# OpenPLCv0_2_0_AnalogueOutput.net
KiCad netlist of a schematic drawn in Altium Designer
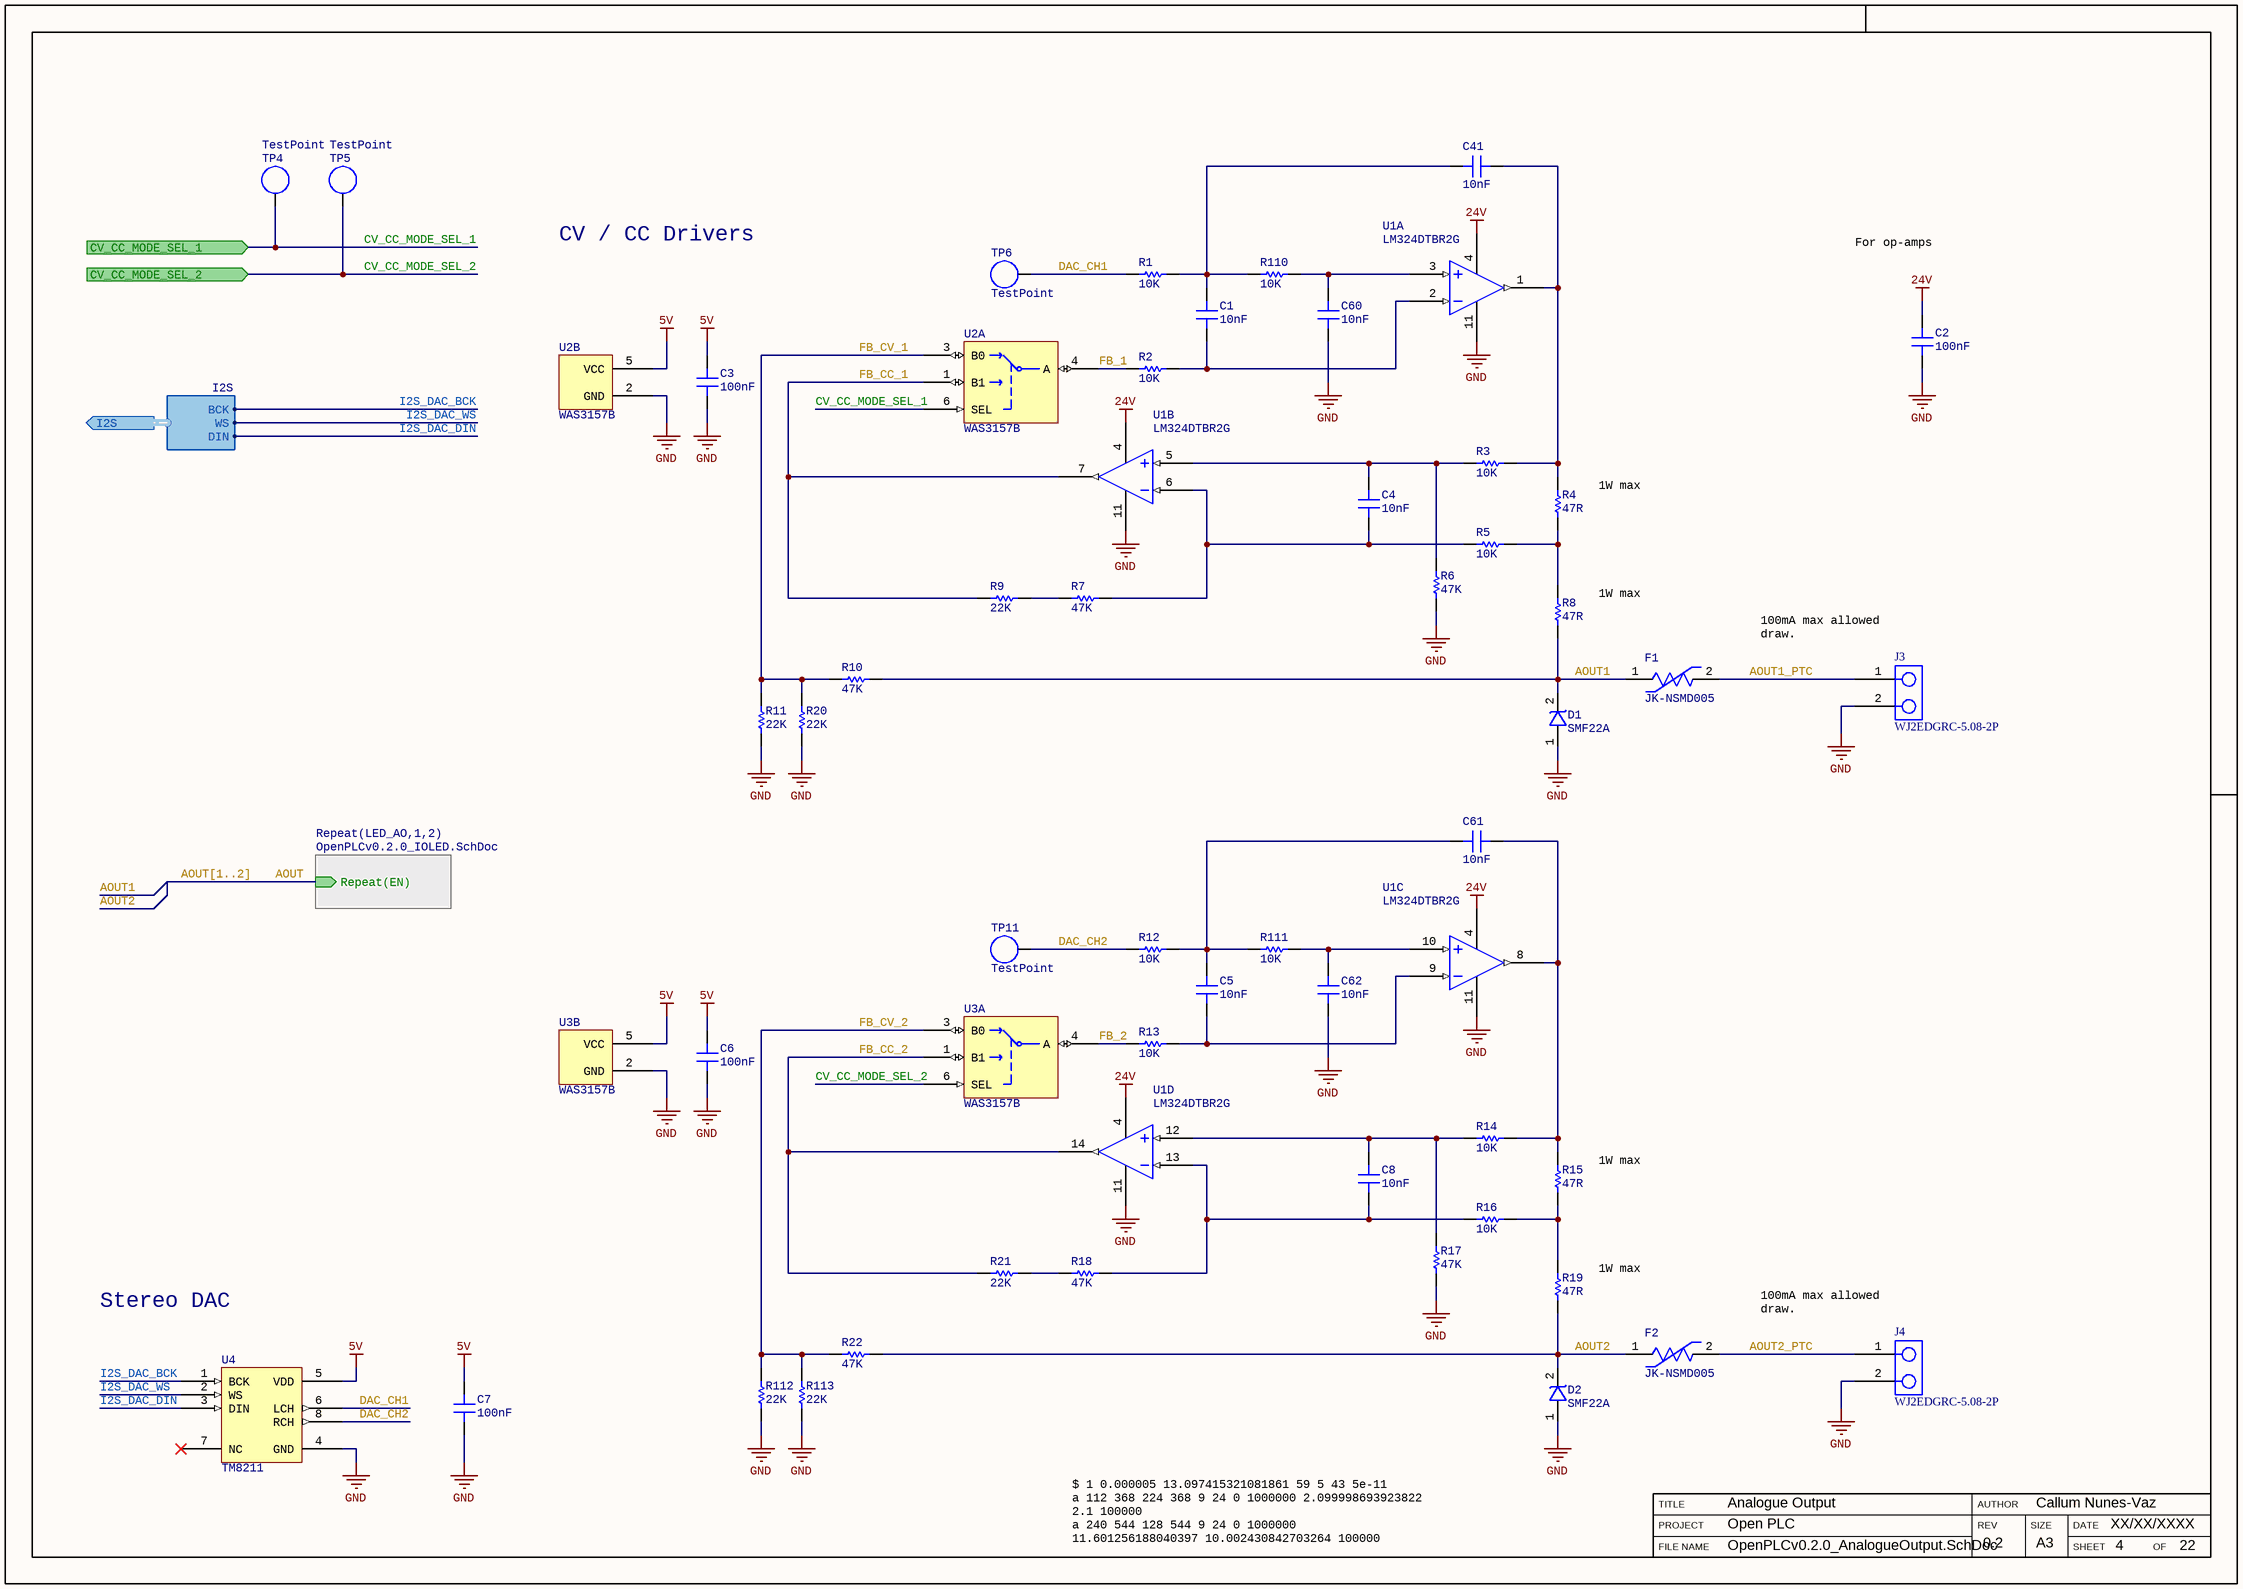
[diagram p0: OpenPLCv0.2.0_AnalogueOutput.SchDoc]

(export (version "E")
  (design (tool "Eeschema 10.0.6"))
  (components
    (comp (ref "C1")
      (value "CC0402KRX7R9BB103")
      (footprint "SMD_CAP_0402(1005)_N")
      (description "10nF ±10% 50V X7R 0402 Multilayer Ceramic Capacitors MLCC - SMD/SMT RoHS")
      (fields (field (name "TOLERANCE") "10%") (field (name "CAPACITANCE") "10nF"))
      (libsource (lib "BrauV2_Capacitor") (part "10nF 0402 50V 10%"))
    )
    (comp (ref "C2")
      (value "CC0402KRX5R9BB104")
      (footprint "SMD_CAP_0402(1005)_N")
      (description "100nF ±10% 50V X5R 0402 Multilayer Ceramic Capacitors MLCC - SMD/SMT RoHS")
      (fields (field (name "TOLERANCE") "10%") (field (name "CAPACITANCE") "100nF"))
      (libsource (lib "BrauV2_Capacitor") (part "100nF 0402 50V 10%"))
    )
    (comp (ref "C3")
      (value "CC0402KRX5R6BB104")
      (footprint "SMD_CAP_0402(1005)_N")
      (description "100nF ±10% 10V X5R 0402 Multilayer Ceramic Capacitors MLCC - SMD/SMT RoHS")
      (fields (field (name "TOLERANCE") "10%") (field (name "CAPACITANCE") "100nF"))
      (libsource (lib "BrauV2_Capacitor") (part "100nF 0402 10V 10%"))
    )
    (comp (ref "C4")
      (value "CC0402KRX7R9BB103")
      (footprint "SMD_CAP_0402(1005)_N")
      (description "10nF ±10% 50V X7R 0402 Multilayer Ceramic Capacitors MLCC - SMD/SMT RoHS")
      (fields (field (name "TOLERANCE") "10%") (field (name "CAPACITANCE") "10nF"))
      (libsource (lib "BrauV2_Capacitor") (part "10nF 0402 50V 10%"))
    )
    (comp (ref "C5")
      (value "CC0402KRX7R9BB103")
      (footprint "SMD_CAP_0402(1005)_N")
      (description "10nF ±10% 50V X7R 0402 Multilayer Ceramic Capacitors MLCC - SMD/SMT RoHS")
      (fields (field (name "TOLERANCE") "10%") (field (name "CAPACITANCE") "10nF"))
      (libsource (lib "BrauV2_Capacitor") (part "10nF 0402 50V 10%"))
    )
    (comp (ref "C6")
      (value "CC0402KRX5R6BB104")
      (footprint "SMD_CAP_0402(1005)_N")
      (description "100nF ±10% 10V X5R 0402 Multilayer Ceramic Capacitors MLCC - SMD/SMT RoHS")
      (fields (field (name "TOLERANCE") "10%") (field (name "CAPACITANCE") "100nF"))
      (libsource (lib "BrauV2_Capacitor") (part "100nF 0402 10V 10%"))
    )
    (comp (ref "C7")
      (value "CC0402KRX5R6BB104")
      (footprint "SMD_CAP_0402(1005)_N")
      (description "100nF ±10% 10V X5R 0402 Multilayer Ceramic Capacitors MLCC - SMD/SMT RoHS")
      (fields (field (name "TOLERANCE") "10%") (field (name "CAPACITANCE") "100nF"))
      (libsource (lib "BrauV2_Capacitor") (part "100nF 0402 10V 10%"))
    )
    (comp (ref "C8")
      (value "CC0402KRX7R9BB103")
      (footprint "SMD_CAP_0402(1005)_N")
      (description "10nF ±10% 50V X7R 0402 Multilayer Ceramic Capacitors MLCC - SMD/SMT RoHS")
      (fields (field (name "TOLERANCE") "10%") (field (name "CAPACITANCE") "10nF"))
      (libsource (lib "BrauV2_Capacitor") (part "10nF 0402 50V 10%"))
    )
    (comp (ref "C41")
      (value "CC0402KRX7R9BB103")
      (footprint "SMD_CAP_0402(1005)_N")
      (description "10nF ±10% 50V X7R 0402 Multilayer Ceramic Capacitors MLCC - SMD/SMT RoHS")
      (fields (field (name "TOLERANCE") "10%") (field (name "CAPACITANCE") "10nF"))
      (libsource (lib "BrauV2_Capacitor") (part "10nF 0402 50V 10%"))
    )
    (comp (ref "C60")
      (value "CC0402KRX7R9BB103")
      (footprint "SMD_CAP_0402(1005)_N")
      (description "10nF ±10% 50V X7R 0402 Multilayer Ceramic Capacitors MLCC - SMD/SMT RoHS")
      (fields (field (name "TOLERANCE") "10%") (field (name "CAPACITANCE") "10nF"))
      (libsource (lib "BrauV2_Capacitor") (part "10nF 0402 50V 10%"))
    )
    (comp (ref "C61")
      (value "CC0402KRX7R9BB103")
      (footprint "SMD_CAP_0402(1005)_N")
      (description "10nF ±10% 50V X7R 0402 Multilayer Ceramic Capacitors MLCC - SMD/SMT RoHS")
      (fields (field (name "TOLERANCE") "10%") (field (name "CAPACITANCE") "10nF"))
      (libsource (lib "BrauV2_Capacitor") (part "10nF 0402 50V 10%"))
    )
    (comp (ref "C62")
      (value "CC0402KRX7R9BB103")
      (footprint "SMD_CAP_0402(1005)_N")
      (description "10nF ±10% 50V X7R 0402 Multilayer Ceramic Capacitors MLCC - SMD/SMT RoHS")
      (fields (field (name "TOLERANCE") "10%") (field (name "CAPACITANCE") "10nF"))
      (libsource (lib "BrauV2_Capacitor") (part "10nF 0402 50V 10%"))
    )
    (comp (ref "D1")
      (value "SMF22A")
      (footprint "SOD-123FL")
      (description "Unidirectional 22V 24.4V 35.5V 5.6A SOD-123F TVS RoHS")
      (libsource (lib "BrauV2") (part "SMF22A"))
    )
    (comp (ref "D2")
      (value "SMF22A")
      (footprint "SOD-123FL")
      (description "Unidirectional 22V 24.4V 35.5V 5.6A SOD-123F TVS RoHS")
      (libsource (lib "BrauV2") (part "SMF22A"))
    )
    (comp (ref "F1")
      (value "JK-NSMD005")
      (footprint "SMD_RES_1206(3216)_N")
      (description "60V 150mA 1.5s 1206 PTC Resettable Fuses RoHS")
      (libsource (lib "BrauV2_Resistor") (part "JK-NSMD005"))
    )
    (comp (ref "F2")
      (value "JK-NSMD005")
      (footprint "SMD_RES_1206(3216)_N")
      (description "60V 150mA 1.5s 1206 PTC Resettable Fuses RoHS")
      (libsource (lib "BrauV2_Resistor") (part "JK-NSMD005"))
    )
    (comp (ref "J3")
      (value "WJ2EDGRC-5.08-2P")
      (footprint "796638-2_BoardEdgeAlt")
      (description "Covered（4Sided） 2 1 0.200\"（5.08mm） 2 P=5.08mm Pluggable System Terminal Block RoHS")
      (libsource (lib "OpenPLCv0.2.0_Connector") (part "WJ2EDGRC-5.08-2P"))
    )
    (comp (ref "J4")
      (value "WJ2EDGRC-5.08-2P")
      (footprint "796638-2_BoardEdgeAlt")
      (description "Covered（4Sided） 2 1 0.200\"（5.08mm） 2 P=5.08mm Pluggable System Terminal Block RoHS")
      (libsource (lib "OpenPLCv0.2.0_Connector") (part "WJ2EDGRC-5.08-2P"))
    )
    (comp (ref "R1")
      (value "RC0402FR-0710KL")
      (footprint "SMD_RES_0402(1005)_N")
      (description "10kΩ ±1% 1/16W ±100ppm/℃ 0402 Chip Resistor - Surface Mount RoHS")
      (fields (field (name "TOLERANCE") "1%") (field (name "RESISTANCE") "10K"))
      (libsource (lib "BrauV2_Resistor") (part "10K 0402 1% 1/16W"))
    )
    (comp (ref "R2")
      (value "RC0402FR-0710KL")
      (footprint "SMD_RES_0402(1005)_N")
      (description "10kΩ ±1% 1/16W ±100ppm/℃ 0402 Chip Resistor - Surface Mount RoHS")
      (fields (field (name "TOLERANCE") "1%") (field (name "RESISTANCE") "10K"))
      (libsource (lib "BrauV2_Resistor") (part "10K 0402 1% 1/16W"))
    )
    (comp (ref "R3")
      (value "RC0402FR-0710KL")
      (footprint "SMD_RES_0402(1005)_N")
      (description "10kΩ ±1% 1/16W ±100ppm/℃ 0402 Chip Resistor - Surface Mount RoHS")
      (fields (field (name "TOLERANCE") "1%") (field (name "RESISTANCE") "10K"))
      (libsource (lib "BrauV2_Resistor") (part "10K 0402 1% 1/16W"))
    )
    (comp (ref "R4")
      (value "AC2512FK-0747RL")
      (footprint "SMD_RES_2512(6432)_N")
      (description "47Ω ±1% 1W ±100ppm/℃ 2512 Chip Resistor - Surface Mount RoHS")
      (fields (field (name "TOLERANCE") "1%") (field (name "RESISTANCE") "47R"))
      (libsource (lib "BrauV2_Resistor") (part "47R 2512 1% 1W"))
    )
    (comp (ref "R5")
      (value "RC0402FR-0710KL")
      (footprint "SMD_RES_0402(1005)_N")
      (description "10kΩ ±1% 1/16W ±100ppm/℃ 0402 Chip Resistor - Surface Mount RoHS")
      (fields (field (name "TOLERANCE") "1%") (field (name "RESISTANCE") "10K"))
      (libsource (lib "BrauV2_Resistor") (part "10K 0402 1% 1/16W"))
    )
    (comp (ref "R6")
      (value "RC0402FR-0747KL")
      (footprint "SMD_RES_0402(1005)_N")
      (description "47kΩ ±1% 1/16W ±100ppm/℃ 0402 Chip Resistor - Surface Mount RoHS")
      (fields (field (name "TOLERANCE") "1%") (field (name "RESISTANCE") "47K"))
      (libsource (lib "BrauV2_Resistor") (part "47K 0402 1% 1/16W"))
    )
    (comp (ref "R7")
      (value "RC0402FR-0747KL")
      (footprint "SMD_RES_0402(1005)_N")
      (description "47kΩ ±1% 1/16W ±100ppm/℃ 0402 Chip Resistor - Surface Mount RoHS")
      (fields (field (name "TOLERANCE") "1%") (field (name "RESISTANCE") "47K"))
      (libsource (lib "BrauV2_Resistor") (part "47K 0402 1% 1/16W"))
    )
    (comp (ref "R8")
      (value "AC2512FK-0747RL")
      (footprint "SMD_RES_2512(6432)_N")
      (description "47Ω ±1% 1W ±100ppm/℃ 2512 Chip Resistor - Surface Mount RoHS")
      (fields (field (name "TOLERANCE") "1%") (field (name "RESISTANCE") "47R"))
      (libsource (lib "BrauV2_Resistor") (part "47R 2512 1% 1W"))
    )
    (comp (ref "R9")
      (value "RC0402FR-0722KL")
      (footprint "SMD_RES_0402(1005)_N")
      (description "22kΩ ±1% 1/16W ±100ppm/℃ 0402 Chip Resistor - Surface Mount RoHS")
      (fields (field (name "TOLERANCE") "1%") (field (name "RESISTANCE") "22K"))
      (libsource (lib "BrauV2_Resistor") (part "22K 0402 1% 1/16W"))
    )
    (comp (ref "R10")
      (value "RC0402FR-0747KL")
      (footprint "SMD_RES_0402(1005)_N")
      (description "47kΩ ±1% 1/16W ±100ppm/℃ 0402 Chip Resistor - Surface Mount RoHS")
      (fields (field (name "TOLERANCE") "1%") (field (name "RESISTANCE") "47K"))
      (libsource (lib "BrauV2_Resistor") (part "47K 0402 1% 1/16W"))
    )
    (comp (ref "R11")
      (value "RC0402FR-0722KL")
      (footprint "SMD_RES_0402(1005)_N")
      (description "22kΩ ±1% 1/16W ±100ppm/℃ 0402 Chip Resistor - Surface Mount RoHS")
      (fields (field (name "TOLERANCE") "1%") (field (name "RESISTANCE") "22K"))
      (libsource (lib "BrauV2_Resistor") (part "22K 0402 1% 1/16W"))
    )
    (comp (ref "R12")
      (value "RC0402FR-0710KL")
      (footprint "SMD_RES_0402(1005)_N")
      (description "10kΩ ±1% 1/16W ±100ppm/℃ 0402 Chip Resistor - Surface Mount RoHS")
      (fields (field (name "TOLERANCE") "1%") (field (name "RESISTANCE") "10K"))
      (libsource (lib "BrauV2_Resistor") (part "10K 0402 1% 1/16W"))
    )
    (comp (ref "R13")
      (value "RC0402FR-0710KL")
      (footprint "SMD_RES_0402(1005)_N")
      (description "10kΩ ±1% 1/16W ±100ppm/℃ 0402 Chip Resistor - Surface Mount RoHS")
      (fields (field (name "TOLERANCE") "1%") (field (name "RESISTANCE") "10K"))
      (libsource (lib "BrauV2_Resistor") (part "10K 0402 1% 1/16W"))
    )
    (comp (ref "R14")
      (value "RC0402FR-0710KL")
      (footprint "SMD_RES_0402(1005)_N")
      (description "10kΩ ±1% 1/16W ±100ppm/℃ 0402 Chip Resistor - Surface Mount RoHS")
      (fields (field (name "TOLERANCE") "1%") (field (name "RESISTANCE") "10K"))
      (libsource (lib "BrauV2_Resistor") (part "10K 0402 1% 1/16W"))
    )
    (comp (ref "R15")
      (value "AC2512FK-0747RL")
      (footprint "SMD_RES_2512(6432)_N")
      (description "47Ω ±1% 1W ±100ppm/℃ 2512 Chip Resistor - Surface Mount RoHS")
      (fields (field (name "TOLERANCE") "1%") (field (name "RESISTANCE") "47R"))
      (libsource (lib "BrauV2_Resistor") (part "47R 2512 1% 1W"))
    )
    (comp (ref "R16")
      (value "RC0402FR-0710KL")
      (footprint "SMD_RES_0402(1005)_N")
      (description "10kΩ ±1% 1/16W ±100ppm/℃ 0402 Chip Resistor - Surface Mount RoHS")
      (fields (field (name "TOLERANCE") "1%") (field (name "RESISTANCE") "10K"))
      (libsource (lib "BrauV2_Resistor") (part "10K 0402 1% 1/16W"))
    )
    (comp (ref "R17")
      (value "RC0402FR-0747KL")
      (footprint "SMD_RES_0402(1005)_N")
      (description "47kΩ ±1% 1/16W ±100ppm/℃ 0402 Chip Resistor - Surface Mount RoHS")
      (fields (field (name "TOLERANCE") "1%") (field (name "RESISTANCE") "47K"))
      (libsource (lib "BrauV2_Resistor") (part "47K 0402 1% 1/16W"))
    )
    (comp (ref "R18")
      (value "RC0402FR-0747KL")
      (footprint "SMD_RES_0402(1005)_N")
      (description "47kΩ ±1% 1/16W ±100ppm/℃ 0402 Chip Resistor - Surface Mount RoHS")
      (fields (field (name "TOLERANCE") "1%") (field (name "RESISTANCE") "47K"))
      (libsource (lib "BrauV2_Resistor") (part "47K 0402 1% 1/16W"))
    )
    (comp (ref "R19")
      (value "AC2512FK-0747RL")
      (footprint "SMD_RES_2512(6432)_N")
      (description "47Ω ±1% 1W ±100ppm/℃ 2512 Chip Resistor - Surface Mount RoHS")
      (fields (field (name "TOLERANCE") "1%") (field (name "RESISTANCE") "47R"))
      (libsource (lib "BrauV2_Resistor") (part "47R 2512 1% 1W"))
    )
    (comp (ref "R20")
      (value "RC0402FR-0722KL")
      (footprint "SMD_RES_0402(1005)_N")
      (description "22kΩ ±1% 1/16W ±100ppm/℃ 0402 Chip Resistor - Surface Mount RoHS")
      (fields (field (name "TOLERANCE") "1%") (field (name "RESISTANCE") "22K"))
      (libsource (lib "BrauV2_Resistor") (part "22K 0402 1% 1/16W"))
    )
    (comp (ref "R21")
      (value "RC0402FR-0722KL")
      (footprint "SMD_RES_0402(1005)_N")
      (description "22kΩ ±1% 1/16W ±100ppm/℃ 0402 Chip Resistor - Surface Mount RoHS")
      (fields (field (name "TOLERANCE") "1%") (field (name "RESISTANCE") "22K"))
      (libsource (lib "BrauV2_Resistor") (part "22K 0402 1% 1/16W"))
    )
    (comp (ref "R22")
      (value "RC0402FR-0747KL")
      (footprint "SMD_RES_0402(1005)_N")
      (description "47kΩ ±1% 1/16W ±100ppm/℃ 0402 Chip Resistor - Surface Mount RoHS")
      (fields (field (name "TOLERANCE") "1%") (field (name "RESISTANCE") "47K"))
      (libsource (lib "BrauV2_Resistor") (part "47K 0402 1% 1/16W"))
    )
    (comp (ref "R110")
      (value "RC0402FR-0710KL")
      (footprint "SMD_RES_0402(1005)_N")
      (description "10kΩ ±1% 1/16W ±100ppm/℃ 0402 Chip Resistor - Surface Mount RoHS")
      (fields (field (name "TOLERANCE") "1%") (field (name "RESISTANCE") "10K"))
      (libsource (lib "BrauV2_Resistor") (part "10K 0402 1% 1/16W"))
    )
    (comp (ref "R111")
      (value "RC0402FR-0710KL")
      (footprint "SMD_RES_0402(1005)_N")
      (description "10kΩ ±1% 1/16W ±100ppm/℃ 0402 Chip Resistor - Surface Mount RoHS")
      (fields (field (name "TOLERANCE") "1%") (field (name "RESISTANCE") "10K"))
      (libsource (lib "BrauV2_Resistor") (part "10K 0402 1% 1/16W"))
    )
    (comp (ref "R112")
      (value "RC0402FR-0722KL")
      (footprint "SMD_RES_0402(1005)_N")
      (description "22kΩ ±1% 1/16W ±100ppm/℃ 0402 Chip Resistor - Surface Mount RoHS")
      (fields (field (name "TOLERANCE") "1%") (field (name "RESISTANCE") "22K"))
      (libsource (lib "BrauV2_Resistor") (part "22K 0402 1% 1/16W"))
    )
    (comp (ref "R113")
      (value "RC0402FR-0722KL")
      (footprint "SMD_RES_0402(1005)_N")
      (description "22kΩ ±1% 1/16W ±100ppm/℃ 0402 Chip Resistor - Surface Mount RoHS")
      (fields (field (name "TOLERANCE") "1%") (field (name "RESISTANCE") "22K"))
      (libsource (lib "BrauV2_Resistor") (part "22K 0402 1% 1/16W"))
    )
    (comp (ref "TP4")
      (value "TestPoint")
      (footprint "Pad")
      (libsource (lib "OpenPLCv0.2.0_Misc") (part "Test point"))
    )
    (comp (ref "TP5")
      (value "TestPoint")
      (footprint "Pad")
      (libsource (lib "OpenPLCv0.2.0_Misc") (part "Test point"))
    )
    (comp (ref "TP6")
      (value "TestPoint")
      (footprint "Pad")
      (libsource (lib "OpenPLCv0.2.0_Misc") (part "Test point"))
    )
    (comp (ref "TP11")
      (value "TestPoint")
      (footprint "Pad")
      (libsource (lib "OpenPLCv0.2.0_Misc") (part "Test point"))
    )
    (comp (ref "U1")
      (value "LM324DTBR2G")
      (footprint "TSSOP-14")
      (description "General Purpose 4 3V ~ 32V, ±1.5V ~ 16V 1MHz 0.6 V/us TSSOP-14 Operational Amplifiers RoHS")
      (libsource (lib "BrauV2_IC") (part "LM324DTBR2G"))
    )
    (comp (ref "U2")
      (value "WAS3157B")
      (footprint "SOT23-6")
      (description "5.5Ω, 400MHz Bandwidth, SPDT Analog Switch SOT23-6")
      (libsource (lib "BrauV2_IC") (part "WAS3157B"))
    )
    (comp (ref "U3")
      (value "WAS3157B")
      (footprint "SOT23-6")
      (description "5.5Ω, 400MHz Bandwidth, SPDT Analog Switch SOT23-6")
      (libsource (lib "BrauV2_IC") (part "WAS3157B"))
    )
    (comp (ref "U4")
      (value "TM8211")
      (footprint "SOIC-8-3.9mm")
      (description "Digital To Analog Converters (DACs) 16bit I2S")
      (libsource (lib "BrauV2_IC") (part "TM8211"))
    )
  )
  (nets
    (net (code "3") (name "/AOUT1") (class "Default")
      (node (ref "D1") (pin "2") (pinfunction "CATHODE_2") (pintype "passive"))
      (node (ref "F1") (pin "1") (pinfunction "1_1") (pintype "passive"))
      (node (ref "R10") (pin "2") (pinfunction "2_2") (pintype "passive"))
      (node (ref "R8") (pin "1") (pinfunction "1_1") (pintype "passive"))
    )
    (net (code "4") (name "/AOUT1_PTC") (class "Default")
      (node (ref "F1") (pin "2") (pinfunction "2_2") (pintype "passive"))
      (node (ref "J3") (pin "1") (pinfunction "1_1") (pintype "passive"))
    )
    (net (code "5") (name "/AOUT2") (class "Default")
      (node (ref "D2") (pin "2") (pinfunction "CATHODE_2") (pintype "passive"))
      (node (ref "F2") (pin "1") (pinfunction "1_1") (pintype "passive"))
      (node (ref "R19") (pin "1") (pinfunction "1_1") (pintype "passive"))
      (node (ref "R22") (pin "2") (pinfunction "2_2") (pintype "passive"))
    )
    (net (code "6") (name "/AOUT2_PTC") (class "Default")
      (node (ref "F2") (pin "2") (pinfunction "2_2") (pintype "passive"))
      (node (ref "J4") (pin "1") (pinfunction "1_1") (pintype "passive"))
    )
    (net (code "8") (name "/CV_CC_MODE_SEL_1") (class "Default")
      (node (ref "TP4") (pin "1") (pinfunction "1_1") (pintype "passive"))
      (node (ref "U2") (pin "6") (pinfunction "SEL_6") (pintype "input"))
    )
    (net (code "9") (name "/CV_CC_MODE_SEL_2") (class "Default")
      (node (ref "TP5") (pin "1") (pinfunction "1_1") (pintype "passive"))
      (node (ref "U3") (pin "6") (pinfunction "SEL_6") (pintype "input"))
    )
    (net (code "10") (name "/DAC_CH1") (class "Default")
      (node (ref "R1") (pin "1") (pinfunction "1_1") (pintype "passive"))
      (node (ref "TP6") (pin "1") (pinfunction "1_1") (pintype "passive"))
      (node (ref "U4") (pin "6") (pinfunction "LCH_6") (pintype "output"))
    )
    (net (code "11") (name "/DAC_CH2") (class "Default")
      (node (ref "R12") (pin "1") (pinfunction "1_1") (pintype "passive"))
      (node (ref "TP11") (pin "1") (pinfunction "1_1") (pintype "passive"))
      (node (ref "U4") (pin "8") (pinfunction "RCH_8") (pintype "output"))
    )
    (net (code "12") (name "/FB_1") (class "Default")
      (node (ref "R2") (pin "1") (pinfunction "1_1") (pintype "passive"))
      (node (ref "U2") (pin "4") (pinfunction "A_4") (pintype "bidirectional"))
    )
    (net (code "13") (name "/FB_2") (class "Default")
      (node (ref "R13") (pin "1") (pinfunction "1_1") (pintype "passive"))
      (node (ref "U3") (pin "4") (pinfunction "A_4") (pintype "bidirectional"))
    )
    (net (code "14") (name "/FB_CC_1") (class "Default")
      (node (ref "R9") (pin "2") (pinfunction "2_2") (pintype "passive"))
      (node (ref "U1") (pin "7") (pinfunction "VOUT_7") (pintype "output"))
      (node (ref "U2") (pin "1") (pinfunction "B1_1") (pintype "bidirectional"))
    )
    (net (code "15") (name "/FB_CC_2") (class "Default")
      (node (ref "R21") (pin "2") (pinfunction "2_2") (pintype "passive"))
      (node (ref "U1") (pin "14") (pinfunction "VOUT_14") (pintype "output"))
      (node (ref "U3") (pin "1") (pinfunction "B1_1") (pintype "bidirectional"))
    )
    (net (code "16") (name "/FB_CV_1") (class "Default")
      (node (ref "R10") (pin "1") (pinfunction "1_1") (pintype "passive"))
      (node (ref "R11") (pin "2") (pinfunction "2_2") (pintype "passive"))
      (node (ref "R20") (pin "2") (pinfunction "2_2") (pintype "passive"))
      (node (ref "U2") (pin "3") (pinfunction "B0_3") (pintype "bidirectional"))
    )
    (net (code "17") (name "/FB_CV_2") (class "Default")
      (node (ref "R112") (pin "2") (pinfunction "2_2") (pintype "passive"))
      (node (ref "R113") (pin "2") (pinfunction "2_2") (pintype "passive"))
      (node (ref "R22") (pin "1") (pinfunction "1_1") (pintype "passive"))
      (node (ref "U3") (pin "3") (pinfunction "B0_3") (pintype "bidirectional"))
    )
    (net (code "18") (name "/I2S_DAC_BCK") (class "Default")
      (node (ref "U4") (pin "1") (pinfunction "BCK_1") (pintype "input"))
    )
    (net (code "19") (name "/I2S_DAC_DIN") (class "Default")
      (node (ref "U4") (pin "3") (pinfunction "DIN_3") (pintype "input"))
    )
    (net (code "20") (name "/I2S_DAC_WS") (class "Default")
      (node (ref "U4") (pin "2") (pinfunction "WS_2") (pintype "input"))
    )
    (net (code "22") (name "5V") (class "Default")
      (node (ref "C3") (pin "2") (pinfunction "2_2") (pintype "passive"))
      (node (ref "C6") (pin "2") (pinfunction "2_2") (pintype "passive"))
      (node (ref "C7") (pin "2") (pinfunction "2_2") (pintype "passive"))
      (node (ref "U2") (pin "5") (pinfunction "VCC_5") (pintype "power_in"))
      (node (ref "U3") (pin "5") (pinfunction "VCC_5") (pintype "power_in"))
      (node (ref "U4") (pin "5") (pinfunction "VDD_5") (pintype "power_in"))
    )
    (net (code "23") (name "24V") (class "Default")
      (node (ref "C2") (pin "2") (pinfunction "2_2") (pintype "passive"))
      (node (ref "U1") (pin "4") (pinfunction "VDD_4") (pintype "power_in"))
    )
    (net (code "24") (name "GND") (class "Default")
      (node (ref "C2") (pin "1") (pinfunction "1_1") (pintype "passive"))
      (node (ref "C3") (pin "1") (pinfunction "1_1") (pintype "passive"))
      (node (ref "C6") (pin "1") (pinfunction "1_1") (pintype "passive"))
      (node (ref "C60") (pin "2") (pinfunction "2_2") (pintype "passive"))
      (node (ref "C62") (pin "2") (pinfunction "2_2") (pintype "passive"))
      (node (ref "C7") (pin "1") (pinfunction "1_1") (pintype "passive"))
      (node (ref "D1") (pin "1") (pinfunction "ANODE_1") (pintype "passive"))
      (node (ref "D2") (pin "1") (pinfunction "ANODE_1") (pintype "passive"))
      (node (ref "J3") (pin "2") (pinfunction "2_2") (pintype "passive"))
      (node (ref "J4") (pin "2") (pinfunction "2_2") (pintype "passive"))
      (node (ref "R11") (pin "1") (pinfunction "1_1") (pintype "passive"))
      (node (ref "R112") (pin "1") (pinfunction "1_1") (pintype "passive"))
      (node (ref "R113") (pin "1") (pinfunction "1_1") (pintype "passive"))
      (node (ref "R17") (pin "1") (pinfunction "1_1") (pintype "passive"))
      (node (ref "R20") (pin "1") (pinfunction "1_1") (pintype "passive"))
      (node (ref "R6") (pin "1") (pinfunction "1_1") (pintype "passive"))
      (node (ref "U1") (pin "11") (pinfunction "VSS_11") (pintype "power_in"))
      (node (ref "U2") (pin "2") (pinfunction "GND_2") (pintype "power_in"))
      (node (ref "U3") (pin "2") (pinfunction "GND_2") (pintype "power_in"))
      (node (ref "U4") (pin "4") (pinfunction "GND_4") (pintype "power_in"))
    )
    (net (code "25") (name "Net-(C1-Pad2)") (class "Default")
      (node (ref "C1") (pin "2") (pinfunction "2_2") (pintype "passive"))
      (node (ref "C41") (pin "2") (pinfunction "2_2") (pintype "passive"))
      (node (ref "R1") (pin "2") (pinfunction "2_2") (pintype "passive"))
      (node (ref "R110") (pin "1") (pinfunction "1_1") (pintype "passive"))
    )
    (net (code "26") (name "Net-(C5-Pad2)") (class "Default")
      (node (ref "C5") (pin "2") (pinfunction "2_2") (pintype "passive"))
      (node (ref "C61") (pin "2") (pinfunction "2_2") (pintype "passive"))
      (node (ref "R111") (pin "1") (pinfunction "1_1") (pintype "passive"))
      (node (ref "R12") (pin "2") (pinfunction "2_2") (pintype "passive"))
    )
    (net (code "27") (name "Net-(R4-Pad1)") (class "Default")
      (node (ref "R4") (pin "1") (pinfunction "1_1") (pintype "passive"))
      (node (ref "R5") (pin "2") (pinfunction "2_2") (pintype "passive"))
      (node (ref "R8") (pin "2") (pinfunction "2_2") (pintype "passive"))
    )
    (net (code "28") (name "Net-(R7-Pad1)") (class "Default")
      (node (ref "R7") (pin "1") (pinfunction "1_1") (pintype "passive"))
      (node (ref "R9") (pin "1") (pinfunction "1_1") (pintype "passive"))
    )
    (net (code "29") (name "Net-(R15-Pad1)") (class "Default")
      (node (ref "R15") (pin "1") (pinfunction "1_1") (pintype "passive"))
      (node (ref "R16") (pin "2") (pinfunction "2_2") (pintype "passive"))
      (node (ref "R19") (pin "2") (pinfunction "2_2") (pintype "passive"))
    )
    (net (code "30") (name "Net-(R18-Pad1)") (class "Default")
      (node (ref "R18") (pin "1") (pinfunction "1_1") (pintype "passive"))
      (node (ref "R21") (pin "1") (pinfunction "1_1") (pintype "passive"))
    )
    (net (code "31") (name "Net-(U1A-VIN+)") (class "Default")
      (node (ref "C60") (pin "1") (pinfunction "1_1") (pintype "passive"))
      (node (ref "R110") (pin "2") (pinfunction "2_2") (pintype "passive"))
      (node (ref "U1") (pin "3") (pinfunction "VIN+_3") (pintype "input"))
    )
    (net (code "32") (name "Net-(U1A-VIN-)") (class "Default")
      (node (ref "C1") (pin "1") (pinfunction "1_1") (pintype "passive"))
      (node (ref "R2") (pin "2") (pinfunction "2_2") (pintype "passive"))
      (node (ref "U1") (pin "2") (pinfunction "VIN-_2") (pintype "input"))
    )
    (net (code "33") (name "Net-(U1A-VOUT)") (class "Default")
      (node (ref "C41") (pin "1") (pinfunction "1_1") (pintype "passive"))
      (node (ref "R3") (pin "2") (pinfunction "2_2") (pintype "passive"))
      (node (ref "R4") (pin "2") (pinfunction "2_2") (pintype "passive"))
      (node (ref "U1") (pin "1") (pinfunction "VOUT_1") (pintype "output"))
    )
    (net (code "34") (name "Net-(U1B-VIN+)") (class "Default")
      (node (ref "C4") (pin "2") (pinfunction "2_2") (pintype "passive"))
      (node (ref "R3") (pin "1") (pinfunction "1_1") (pintype "passive"))
      (node (ref "R6") (pin "2") (pinfunction "2_2") (pintype "passive"))
      (node (ref "U1") (pin "5") (pinfunction "VIN+_5") (pintype "input"))
    )
    (net (code "35") (name "Net-(U1B-VIN-)") (class "Default")
      (node (ref "C4") (pin "1") (pinfunction "1_1") (pintype "passive"))
      (node (ref "R5") (pin "1") (pinfunction "1_1") (pintype "passive"))
      (node (ref "R7") (pin "2") (pinfunction "2_2") (pintype "passive"))
      (node (ref "U1") (pin "6") (pinfunction "VIN-_6") (pintype "input"))
    )
    (net (code "36") (name "Net-(U1C-VIN+)") (class "Default")
      (node (ref "C62") (pin "1") (pinfunction "1_1") (pintype "passive"))
      (node (ref "R111") (pin "2") (pinfunction "2_2") (pintype "passive"))
      (node (ref "U1") (pin "10") (pinfunction "VIN+_10") (pintype "input"))
    )
    (net (code "37") (name "Net-(U1C-VIN-)") (class "Default")
      (node (ref "C5") (pin "1") (pinfunction "1_1") (pintype "passive"))
      (node (ref "R13") (pin "2") (pinfunction "2_2") (pintype "passive"))
      (node (ref "U1") (pin "9") (pinfunction "VIN-_9") (pintype "input"))
    )
    (net (code "38") (name "Net-(U1C-VOUT)") (class "Default")
      (node (ref "C61") (pin "1") (pinfunction "1_1") (pintype "passive"))
      (node (ref "R14") (pin "2") (pinfunction "2_2") (pintype "passive"))
      (node (ref "R15") (pin "2") (pinfunction "2_2") (pintype "passive"))
      (node (ref "U1") (pin "8") (pinfunction "VOUT_8") (pintype "output"))
    )
    (net (code "39") (name "Net-(U1D-VIN+)") (class "Default")
      (node (ref "C8") (pin "2") (pinfunction "2_2") (pintype "passive"))
      (node (ref "R14") (pin "1") (pinfunction "1_1") (pintype "passive"))
      (node (ref "R17") (pin "2") (pinfunction "2_2") (pintype "passive"))
      (node (ref "U1") (pin "12") (pinfunction "VIN+_12") (pintype "input"))
    )
    (net (code "40") (name "Net-(U1D-VIN-)") (class "Default")
      (node (ref "C8") (pin "1") (pinfunction "1_1") (pintype "passive"))
      (node (ref "R16") (pin "1") (pinfunction "1_1") (pintype "passive"))
      (node (ref "R18") (pin "2") (pinfunction "2_2") (pintype "passive"))
      (node (ref "U1") (pin "13") (pinfunction "VIN-_13") (pintype "input"))
    )
    (net (code "41") (name "unconnected-(U4-NC-Pad7)") (class "Default")
      (node (ref "U4") (pin "7") (pinfunction "NC_7") (pintype "passive+no_connect"))
    )
  )
)
